# DigiDice.net
KiCad netlist of a schematic drawn in EAGLE
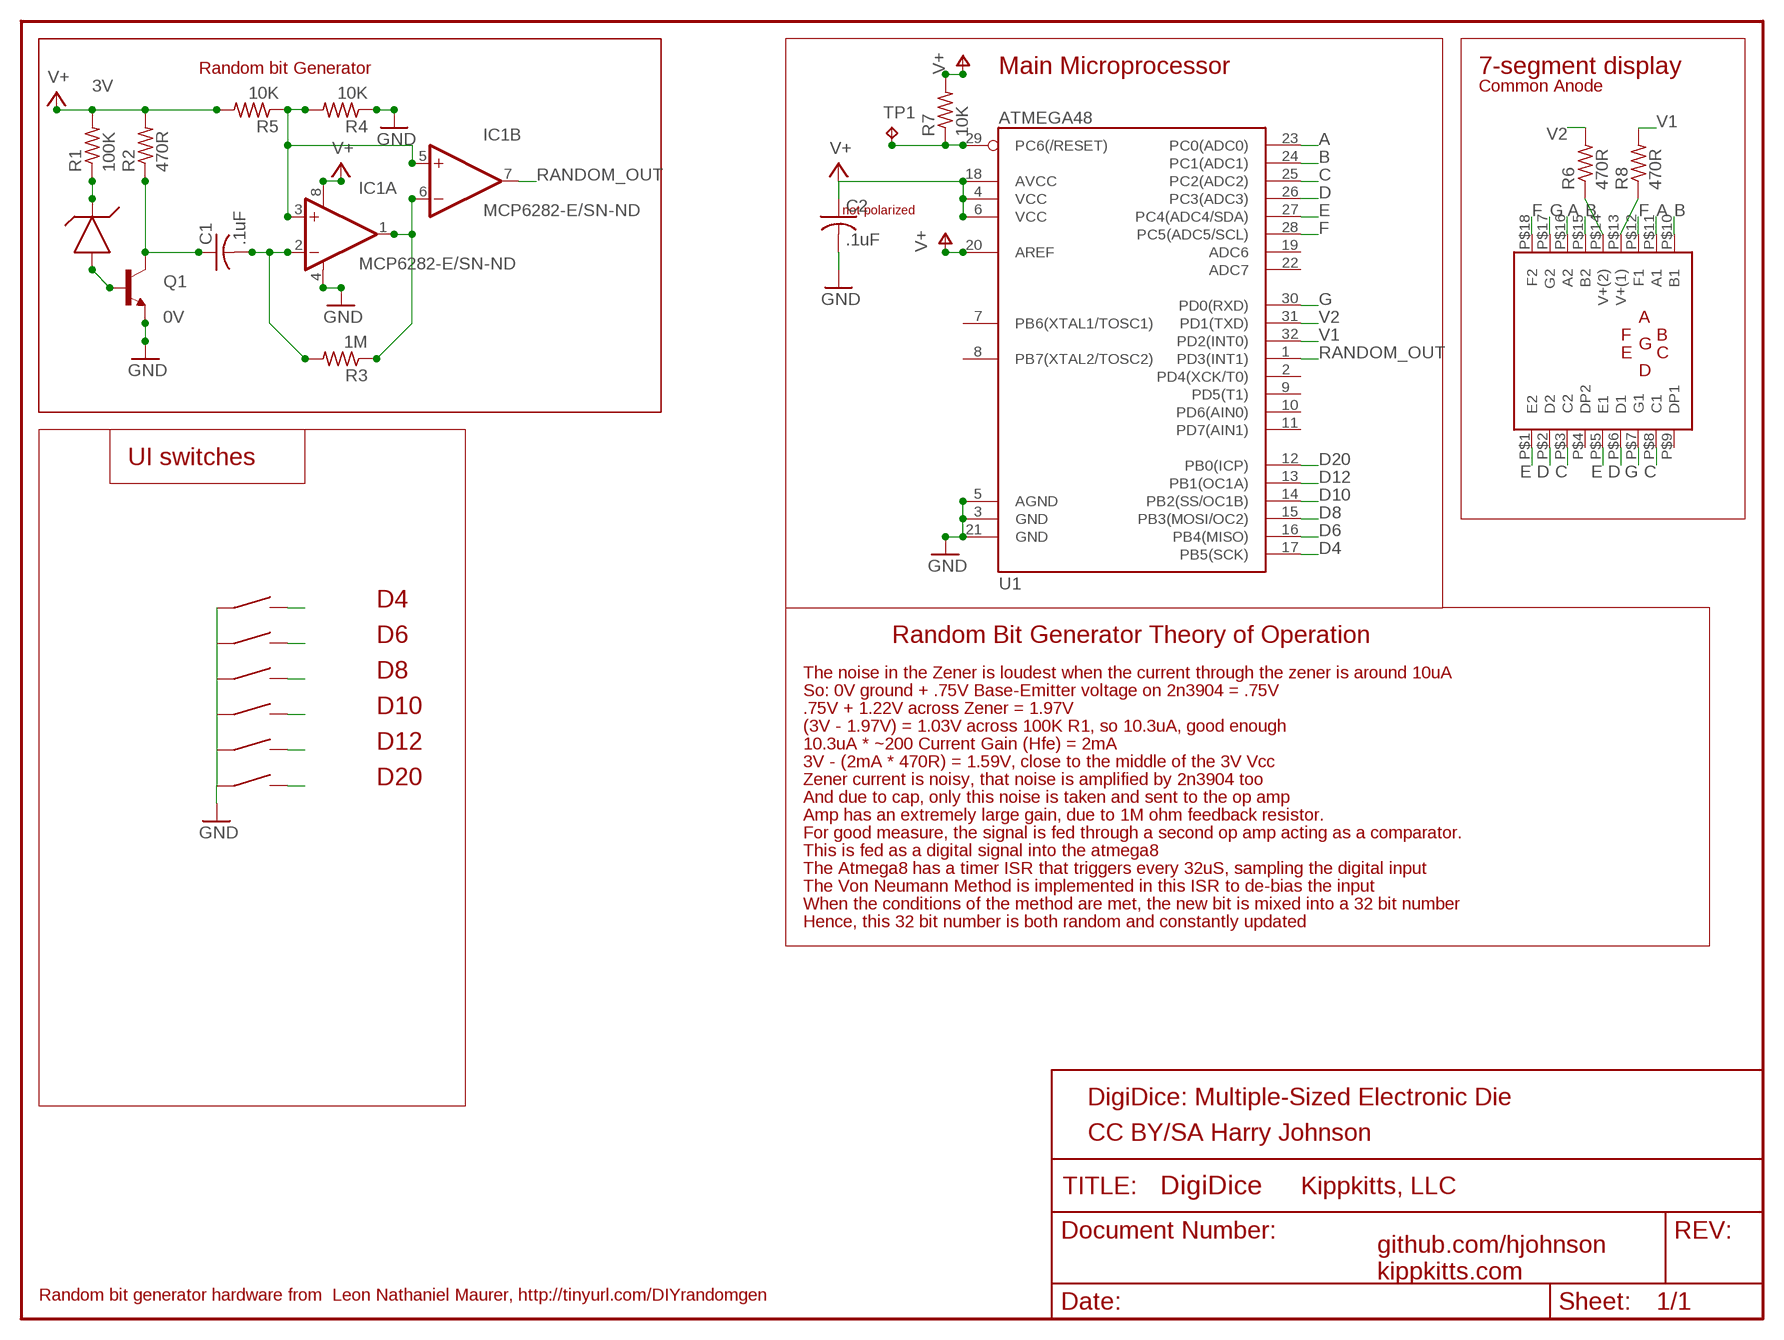
[diagram p0: schematic, sheet 1]

(export (version "E")
  (design (tool "Eeschema 10.0.6"))
  (components
    (comp (ref "C1")
      (value ".1uF")
      (footprint "eagle-import:C0805")
      (libsource (lib "eagle-import") (part "C-USC0805"))
    )
    (comp (ref "C2")
      (value ".1uF")
      (footprint "eagle-import:C0805")
      (libsource (lib "eagle-import") (part "C-USC0805"))
    )
    (comp (ref "IC1")
      (value "MCP6282-E/SN-ND")
      (footprint "eagle-import:SO08")
      (fields (field (name "MF") "TEXAS INSTRUMENTS") (field (name "MPN") "OPA2340UA"))
      (libsource (lib "eagle-import") (part "OPA2340U"))
    )
    (comp (ref "Q1")
      (value "TRANSISTOR_NPNSOT23")
      (footprint "eagle-import:SOT23")
      (libsource (lib "eagle-import") (part "TRANSISTOR_NPNSOT23"))
    )
    (comp (ref "R1")
      (value "100K")
      (footprint "eagle-import:R0805")
      (libsource (lib "eagle-import") (part "R-US_R0805"))
    )
    (comp (ref "R2")
      (value "470R")
      (footprint "eagle-import:R0805")
      (libsource (lib "eagle-import") (part "R-US_R0805"))
    )
    (comp (ref "R3")
      (value "1M")
      (footprint "eagle-import:R0805")
      (libsource (lib "eagle-import") (part "R-US_R0805"))
    )
    (comp (ref "R4")
      (value "10K")
      (footprint "eagle-import:R0805")
      (libsource (lib "eagle-import") (part "R-US_R0805"))
    )
    (comp (ref "R5")
      (value "10K")
      (footprint "eagle-import:R0805")
      (libsource (lib "eagle-import") (part "R-US_R0805"))
    )
    (comp (ref "R6")
      (value "470R")
      (footprint "eagle-import:R0805")
      (libsource (lib "eagle-import") (part "R-US_R0805"))
    )
    (comp (ref "R7")
      (value "10K")
      (footprint "eagle-import:R0805")
      (libsource (lib "eagle-import") (part "R-US_R0805"))
    )
    (comp (ref "R8")
      (value "470R")
      (footprint "eagle-import:R0805")
      (libsource (lib "eagle-import") (part "R-US_R0805"))
    )
    (comp (ref "SW1")
      (value "SPST_SWITCH")
      (footprint "eagle-import:EG2513-ND")
      (libsource (lib "eagle-import") (part "SPST_SWITCH"))
    )
    (comp (ref "SW2")
      (value "SPST_SWITCH")
      (footprint "eagle-import:EG2513-ND")
      (libsource (lib "eagle-import") (part "SPST_SWITCH"))
    )
    (comp (ref "SW3")
      (value "SPST_SWITCH")
      (footprint "eagle-import:EG2513-ND")
      (libsource (lib "eagle-import") (part "SPST_SWITCH"))
    )
    (comp (ref "SW4")
      (value "SPST_SWITCH")
      (footprint "eagle-import:EG2513-ND")
      (libsource (lib "eagle-import") (part "SPST_SWITCH"))
    )
    (comp (ref "SW5")
      (value "SPST_SWITCH")
      (footprint "eagle-import:EG2513-ND")
      (libsource (lib "eagle-import") (part "SPST_SWITCH"))
    )
    (comp (ref "SW6")
      (value "SPST_SWITCH")
      (footprint "eagle-import:EG2513-ND")
      (libsource (lib "eagle-import") (part "SPST_SWITCH"))
    )
    (comp (ref "TP1")
      (value "TPB1,27")
      (footprint "eagle-import:B1,27")
      (libsource (lib "eagle-import") (part "TPB1,27"))
    )
    (comp (ref "U$1")
      (value "ZXRE1004FFTA")
      (footprint "eagle-import:SOT23")
      (libsource (lib "eagle-import") (part "ZXRE1004FFTA"))
    )
    (comp (ref "U$2")
      (value "2DIGIT_7SEGMENT")
      (footprint "eagle-import:HDSP-521E")
      (libsource (lib "eagle-import") (part "2DIGIT_7SEGMENT"))
    )
    (comp (ref "U1")
      (value "ATMEGA48")
      (footprint "eagle-import:TQFP32-08")
      (libsource (lib "eagle-import") (part "ATMEGA168"))
    )
  )
  (nets
    (net (code "1") (name "/A") (class "Default")
      (node (ref "U$2") (pin "P$11") (pinfunction "A1_P$11") (pintype "bidirectional"))
      (node (ref "U$2") (pin "P$16") (pinfunction "A2_P$16") (pintype "bidirectional"))
      (node (ref "U1") (pin "23") (pinfunction "PC0(ADC0)_23") (pintype "bidirectional"))
    )
    (net (code "2") (name "/B") (class "Default")
      (node (ref "U$2") (pin "P$10") (pinfunction "B1_P$10") (pintype "bidirectional"))
      (node (ref "U$2") (pin "P$15") (pinfunction "B2_P$15") (pintype "bidirectional"))
      (node (ref "U1") (pin "24") (pinfunction "PC1(ADC1)_24") (pintype "bidirectional"))
    )
    (net (code "3") (name "/C") (class "Default")
      (node (ref "U$2") (pin "P$3") (pinfunction "C2_P$3") (pintype "bidirectional"))
      (node (ref "U$2") (pin "P$8") (pinfunction "C1_P$8") (pintype "bidirectional"))
      (node (ref "U1") (pin "25") (pinfunction "PC2(ADC2)_25") (pintype "bidirectional"))
    )
    (net (code "4") (name "/D") (class "Default")
      (node (ref "U$2") (pin "P$2") (pinfunction "D2_P$2") (pintype "bidirectional"))
      (node (ref "U$2") (pin "P$6") (pinfunction "D1_P$6") (pintype "bidirectional"))
      (node (ref "U1") (pin "26") (pinfunction "PC3(ADC3)_26") (pintype "bidirectional"))
    )
    (net (code "5") (name "/D4") (class "Default")
      (node (ref "SW1") (pin "P$2") (pinfunction "2_P$2") (pintype "bidirectional"))
      (node (ref "U1") (pin "17") (pinfunction "PB5(SCK)_17") (pintype "bidirectional"))
    )
    (net (code "6") (name "/D6") (class "Default")
      (node (ref "SW2") (pin "P$2") (pinfunction "2_P$2") (pintype "bidirectional"))
      (node (ref "U1") (pin "16") (pinfunction "PB4(MISO)_16") (pintype "bidirectional"))
    )
    (net (code "7") (name "/D8") (class "Default")
      (node (ref "SW3") (pin "P$2") (pinfunction "2_P$2") (pintype "bidirectional"))
      (node (ref "U1") (pin "15") (pinfunction "PB3(MOSI/OC2)_15") (pintype "bidirectional"))
    )
    (net (code "8") (name "/D10") (class "Default")
      (node (ref "SW4") (pin "P$2") (pinfunction "2_P$2") (pintype "bidirectional"))
      (node (ref "U1") (pin "14") (pinfunction "PB2(SS/OC1B)_14") (pintype "bidirectional"))
    )
    (net (code "9") (name "/D12") (class "Default")
      (node (ref "SW5") (pin "P$2") (pinfunction "2_P$2") (pintype "bidirectional"))
      (node (ref "U1") (pin "13") (pinfunction "PB1(OC1A)_13") (pintype "bidirectional"))
    )
    (net (code "10") (name "/D20") (class "Default")
      (node (ref "SW6") (pin "P$2") (pinfunction "2_P$2") (pintype "bidirectional"))
      (node (ref "U1") (pin "12") (pinfunction "PB0(ICP)_12") (pintype "bidirectional"))
    )
    (net (code "11") (name "/E") (class "Default")
      (node (ref "U$2") (pin "P$1") (pinfunction "E2_P$1") (pintype "bidirectional"))
      (node (ref "U$2") (pin "P$5") (pinfunction "E1_P$5") (pintype "bidirectional"))
      (node (ref "U1") (pin "27") (pinfunction "PC4(ADC4/SDA)_27") (pintype "bidirectional"))
    )
    (net (code "12") (name "/F") (class "Default")
      (node (ref "U$2") (pin "P$12") (pinfunction "F1_P$12") (pintype "bidirectional"))
      (node (ref "U$2") (pin "P$18") (pinfunction "F2_P$18") (pintype "bidirectional"))
      (node (ref "U1") (pin "28") (pinfunction "PC5(ADC5/SCL)_28") (pintype "bidirectional"))
    )
    (net (code "13") (name "/G") (class "Default")
      (node (ref "U$2") (pin "P$17") (pinfunction "G2_P$17") (pintype "bidirectional"))
      (node (ref "U$2") (pin "P$7") (pinfunction "G1_P$7") (pintype "bidirectional"))
      (node (ref "U1") (pin "30") (pinfunction "PD0(RXD)_30") (pintype "bidirectional"))
    )
    (net (code "14") (name "/RANDOM_OUT") (class "Default")
      (node (ref "IC1") (pin "7") (pinfunction "OUT_7") (pintype "output"))
      (node (ref "U1") (pin "1") (pinfunction "PD3(INT1)_1") (pintype "bidirectional"))
    )
    (net (code "15") (name "/V1") (class "Default")
      (node (ref "R8") (pin "2") (pinfunction "2_2") (pintype "passive"))
      (node (ref "U1") (pin "32") (pinfunction "PD2(INT0)_32") (pintype "bidirectional"))
    )
    (net (code "16") (name "/V2") (class "Default")
      (node (ref "R6") (pin "2") (pinfunction "2_2") (pintype "passive"))
      (node (ref "U1") (pin "31") (pinfunction "PD1(TXD)_31") (pintype "bidirectional"))
    )
    (net (code "17") (name "GND") (class "Default")
      (node (ref "C2") (pin "2") (pinfunction "2_2") (pintype "passive"))
      (node (ref "IC1") (pin "4") (pinfunction "V-_4") (pintype "power_in"))
      (node (ref "Q1") (pin "2") (pinfunction "E_2") (pintype "passive"))
      (node (ref "R4") (pin "1") (pinfunction "1_1") (pintype "passive"))
      (node (ref "SW1") (pin "P$1") (pinfunction "1_P$1") (pintype "bidirectional"))
      (node (ref "SW2") (pin "P$1") (pinfunction "1_P$1") (pintype "bidirectional"))
      (node (ref "SW3") (pin "P$1") (pinfunction "1_P$1") (pintype "bidirectional"))
      (node (ref "SW4") (pin "P$1") (pinfunction "1_P$1") (pintype "bidirectional"))
      (node (ref "SW5") (pin "P$1") (pinfunction "1_P$1") (pintype "bidirectional"))
      (node (ref "SW6") (pin "P$1") (pinfunction "1_P$1") (pintype "bidirectional"))
      (node (ref "U1") (pin "21") (pinfunction "GND_21") (pintype "bidirectional"))
      (node (ref "U1") (pin "3") (pinfunction "GND_3") (pintype "bidirectional"))
      (node (ref "U1") (pin "5") (pinfunction "AGND_5") (pintype "bidirectional"))
    )
    (net (code "18") (name "Net-(IC1A-+IN)") (class "Default")
      (node (ref "IC1") (pin "3") (pinfunction "+IN_3") (pintype "input"))
      (node (ref "IC1") (pin "5") (pinfunction "+IN_5") (pintype "input"))
      (node (ref "R4") (pin "2") (pinfunction "2_2") (pintype "passive"))
      (node (ref "R5") (pin "1") (pinfunction "1_1") (pintype "passive"))
    )
    (net (code "19") (name "Net-(IC1A--IN)") (class "Default")
      (node (ref "C1") (pin "2") (pinfunction "2_2") (pintype "passive"))
      (node (ref "IC1") (pin "2") (pinfunction "-IN_2") (pintype "input"))
      (node (ref "R3") (pin "2") (pinfunction "2_2") (pintype "passive"))
    )
    (net (code "20") (name "Net-(IC1A-OUT)") (class "Default")
      (node (ref "IC1") (pin "1") (pinfunction "OUT_1") (pintype "output"))
      (node (ref "IC1") (pin "6") (pinfunction "-IN_6") (pintype "input"))
      (node (ref "R3") (pin "1") (pinfunction "1_1") (pintype "passive"))
    )
    (net (code "21") (name "Net-(Q1-B)") (class "Default")
      (node (ref "Q1") (pin "1") (pinfunction "B_1") (pintype "passive"))
      (node (ref "U$1") (pin "2") (pinfunction "A_2") (pintype "bidirectional"))
    )
    (net (code "22") (name "Net-(Q1-C)") (class "Default")
      (node (ref "C1") (pin "1") (pinfunction "1_1") (pintype "passive"))
      (node (ref "Q1") (pin "3") (pinfunction "C_3") (pintype "passive"))
      (node (ref "R2") (pin "1") (pinfunction "1_1") (pintype "passive"))
    )
    (net (code "23") (name "Net-(U$1-K)") (class "Default")
      (node (ref "R1") (pin "1") (pinfunction "1_1") (pintype "passive"))
      (node (ref "U$1") (pin "1") (pinfunction "K_1") (pintype "bidirectional"))
    )
    (net (code "24") (name "Net-(U$2-V+(1))") (class "Default")
      (node (ref "R8") (pin "1") (pinfunction "1_1") (pintype "passive"))
      (node (ref "U$2") (pin "P$13") (pinfunction "V+(1)_P$13") (pintype "bidirectional"))
    )
    (net (code "25") (name "Net-(U$2-V+(2))") (class "Default")
      (node (ref "R6") (pin "1") (pinfunction "1_1") (pintype "passive"))
      (node (ref "U$2") (pin "P$14") (pinfunction "V+(2)_P$14") (pintype "bidirectional"))
    )
    (net (code "26") (name "Net-(U1-PC6({slash}RESET))") (class "Default")
      (node (ref "R7") (pin "1") (pinfunction "1_1") (pintype "passive"))
      (node (ref "TP1") (pin "TP") (pinfunction "TP_TP") (pintype "input"))
      (node (ref "U1") (pin "29") (pinfunction "PC6(/RESET)_29") (pintype "bidirectional"))
    )
    (net (code "27") (name "V+") (class "Default")
      (node (ref "C2") (pin "1") (pinfunction "1_1") (pintype "passive"))
      (node (ref "IC1") (pin "8") (pinfunction "V+_8") (pintype "power_in"))
      (node (ref "R1") (pin "2") (pinfunction "2_2") (pintype "passive"))
      (node (ref "R2") (pin "2") (pinfunction "2_2") (pintype "passive"))
      (node (ref "R5") (pin "2") (pinfunction "2_2") (pintype "passive"))
      (node (ref "R7") (pin "2") (pinfunction "2_2") (pintype "passive"))
      (node (ref "U1") (pin "18") (pinfunction "AVCC_18") (pintype "bidirectional"))
      (node (ref "U1") (pin "20") (pinfunction "AREF_20") (pintype "bidirectional"))
      (node (ref "U1") (pin "4") (pinfunction "VCC_4") (pintype "bidirectional"))
      (node (ref "U1") (pin "6") (pinfunction "VCC_6") (pintype "bidirectional"))
    )
    (net (code "28") (name "unconnected-(U$2-DP1-PadP$9)") (class "Default")
      (node (ref "U$2") (pin "P$9") (pinfunction "DP1_P$9") (pintype "bidirectional"))
    )
    (net (code "29") (name "unconnected-(U$2-DP2-PadP$4)") (class "Default")
      (node (ref "U$2") (pin "P$4") (pinfunction "DP2_P$4") (pintype "bidirectional"))
    )
    (net (code "30") (name "unconnected-(U1-ADC6-Pad19)") (class "Default")
      (node (ref "U1") (pin "19") (pinfunction "ADC6_19") (pintype "bidirectional"))
    )
    (net (code "31") (name "unconnected-(U1-ADC7-Pad22)") (class "Default")
      (node (ref "U1") (pin "22") (pinfunction "ADC7_22") (pintype "bidirectional"))
    )
    (net (code "32") (name "unconnected-(U1-PB6(XTAL1{slash}TOSC1)-Pad7)") (class "Default")
      (node (ref "U1") (pin "7") (pinfunction "PB6(XTAL1/TOSC1)_7") (pintype "bidirectional"))
    )
    (net (code "33") (name "unconnected-(U1-PB7(XTAL2{slash}TOSC2)-Pad8)") (class "Default")
      (node (ref "U1") (pin "8") (pinfunction "PB7(XTAL2/TOSC2)_8") (pintype "bidirectional"))
    )
    (net (code "34") (name "unconnected-(U1-PD4(XCK{slash}T0)-Pad2)") (class "Default")
      (node (ref "U1") (pin "2") (pinfunction "PD4(XCK/T0)_2") (pintype "bidirectional"))
    )
    (net (code "35") (name "unconnected-(U1-PD5(T1)-Pad9)") (class "Default")
      (node (ref "U1") (pin "9") (pinfunction "PD5(T1)_9") (pintype "bidirectional"))
    )
    (net (code "36") (name "unconnected-(U1-PD6(AIN0)-Pad10)") (class "Default")
      (node (ref "U1") (pin "10") (pinfunction "PD6(AIN0)_10") (pintype "bidirectional"))
    )
    (net (code "37") (name "unconnected-(U1-PD7(AIN1)-Pad11)") (class "Default")
      (node (ref "U1") (pin "11") (pinfunction "PD7(AIN1)_11") (pintype "bidirectional"))
    )
  )
)
